# BMS.net
KiCad netlist of a schematic drawn in Altium Designer
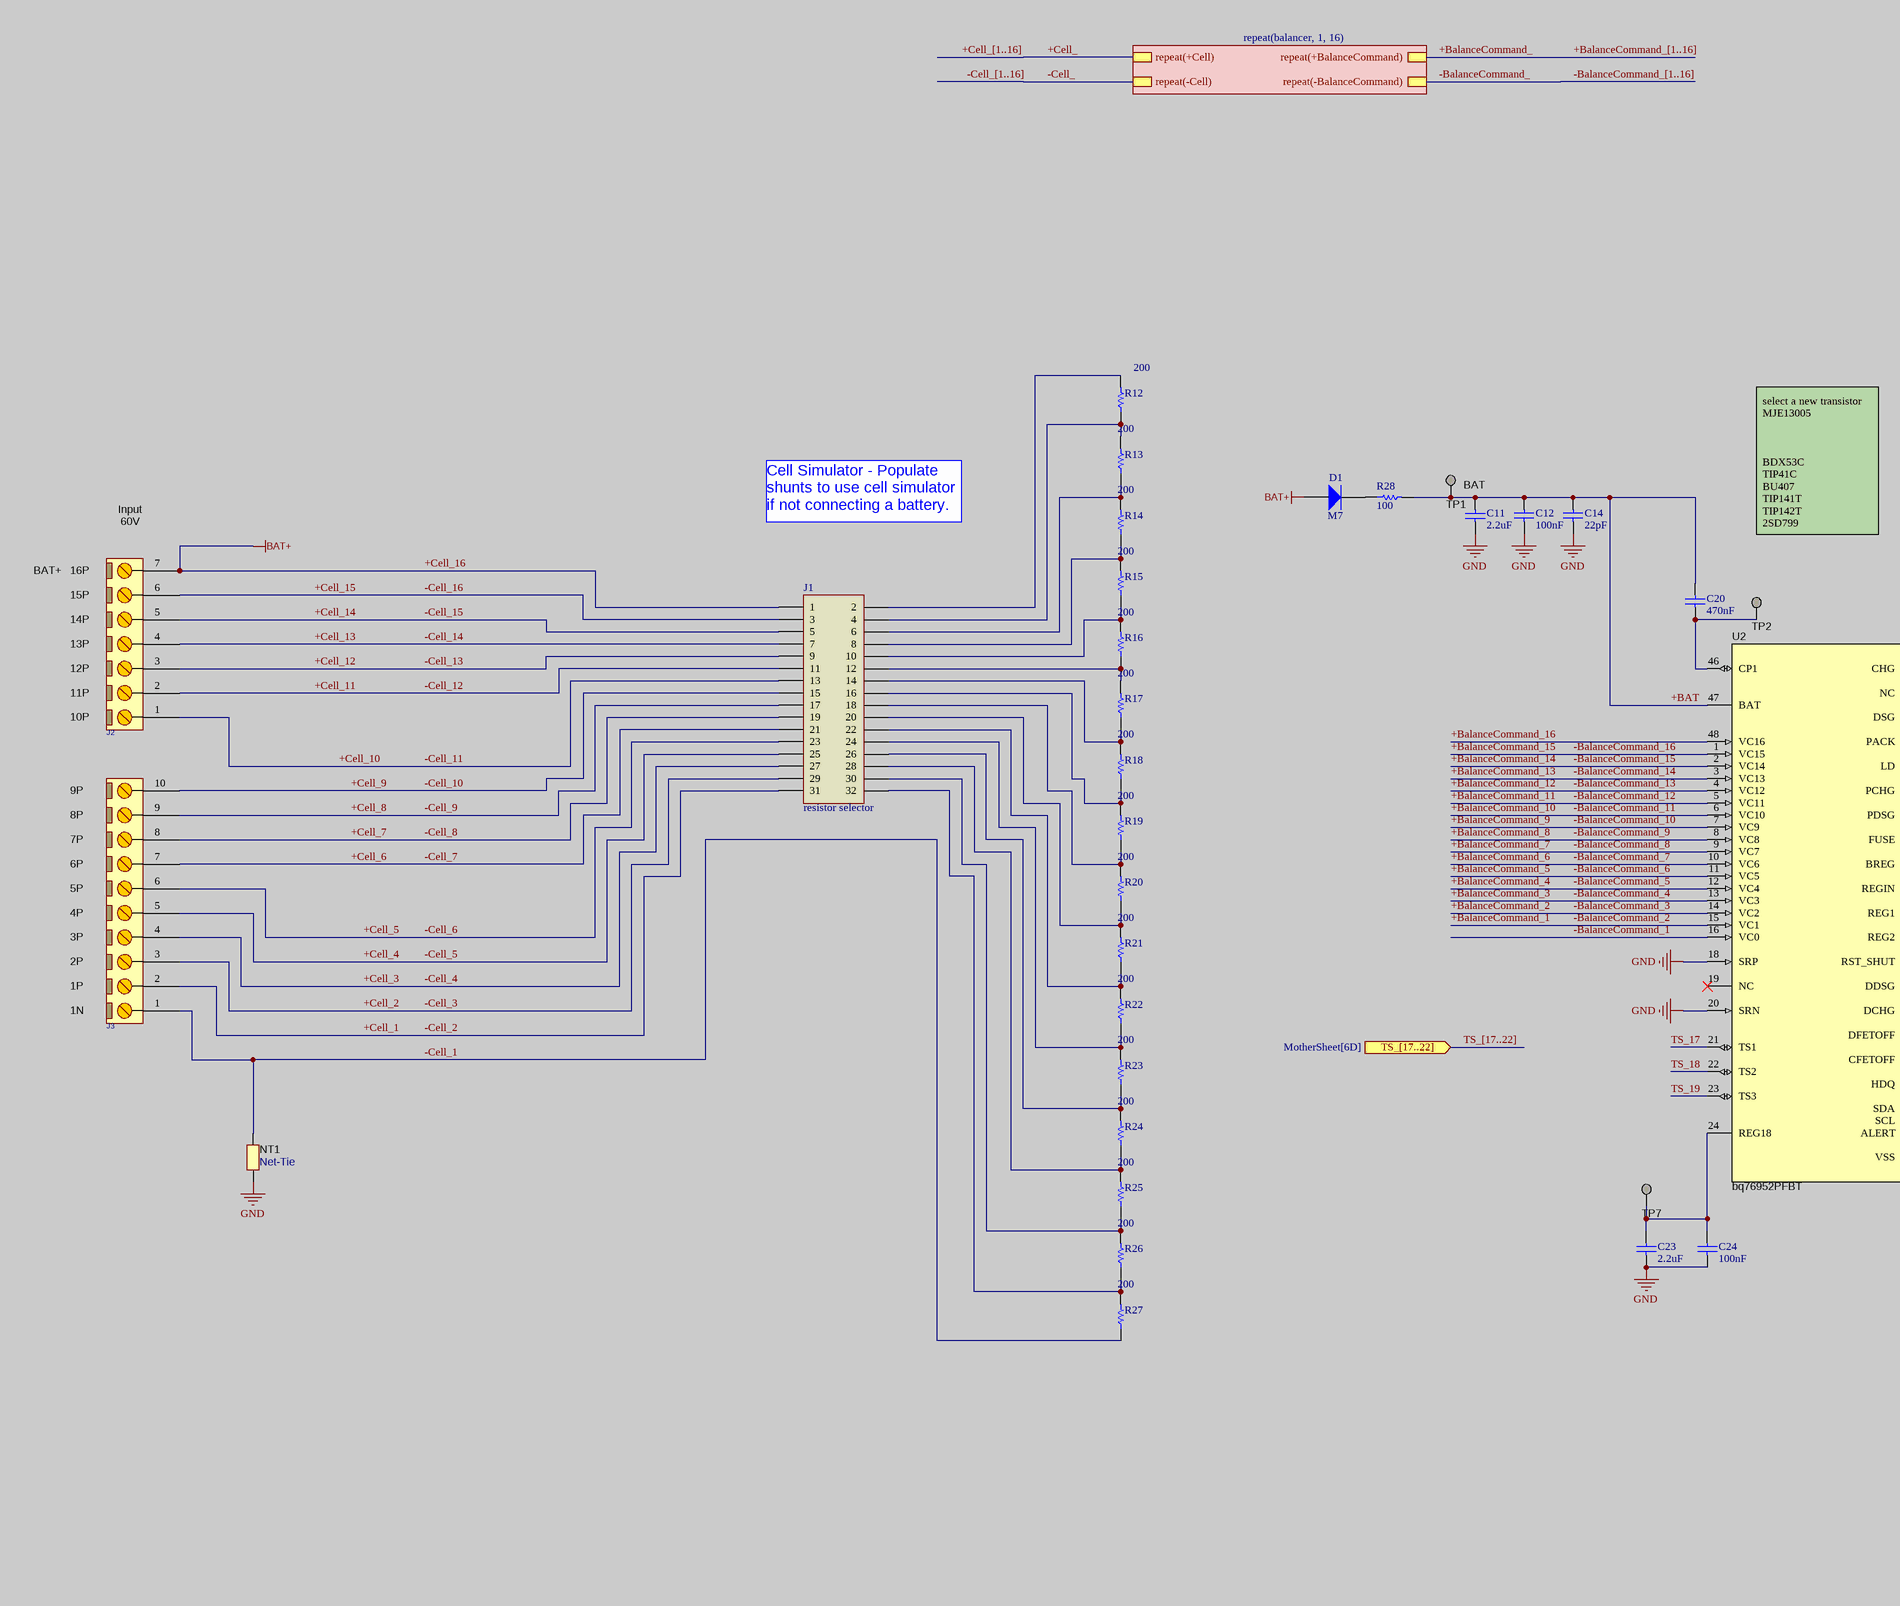
[diagram p0: BMS.SchDoc, left]
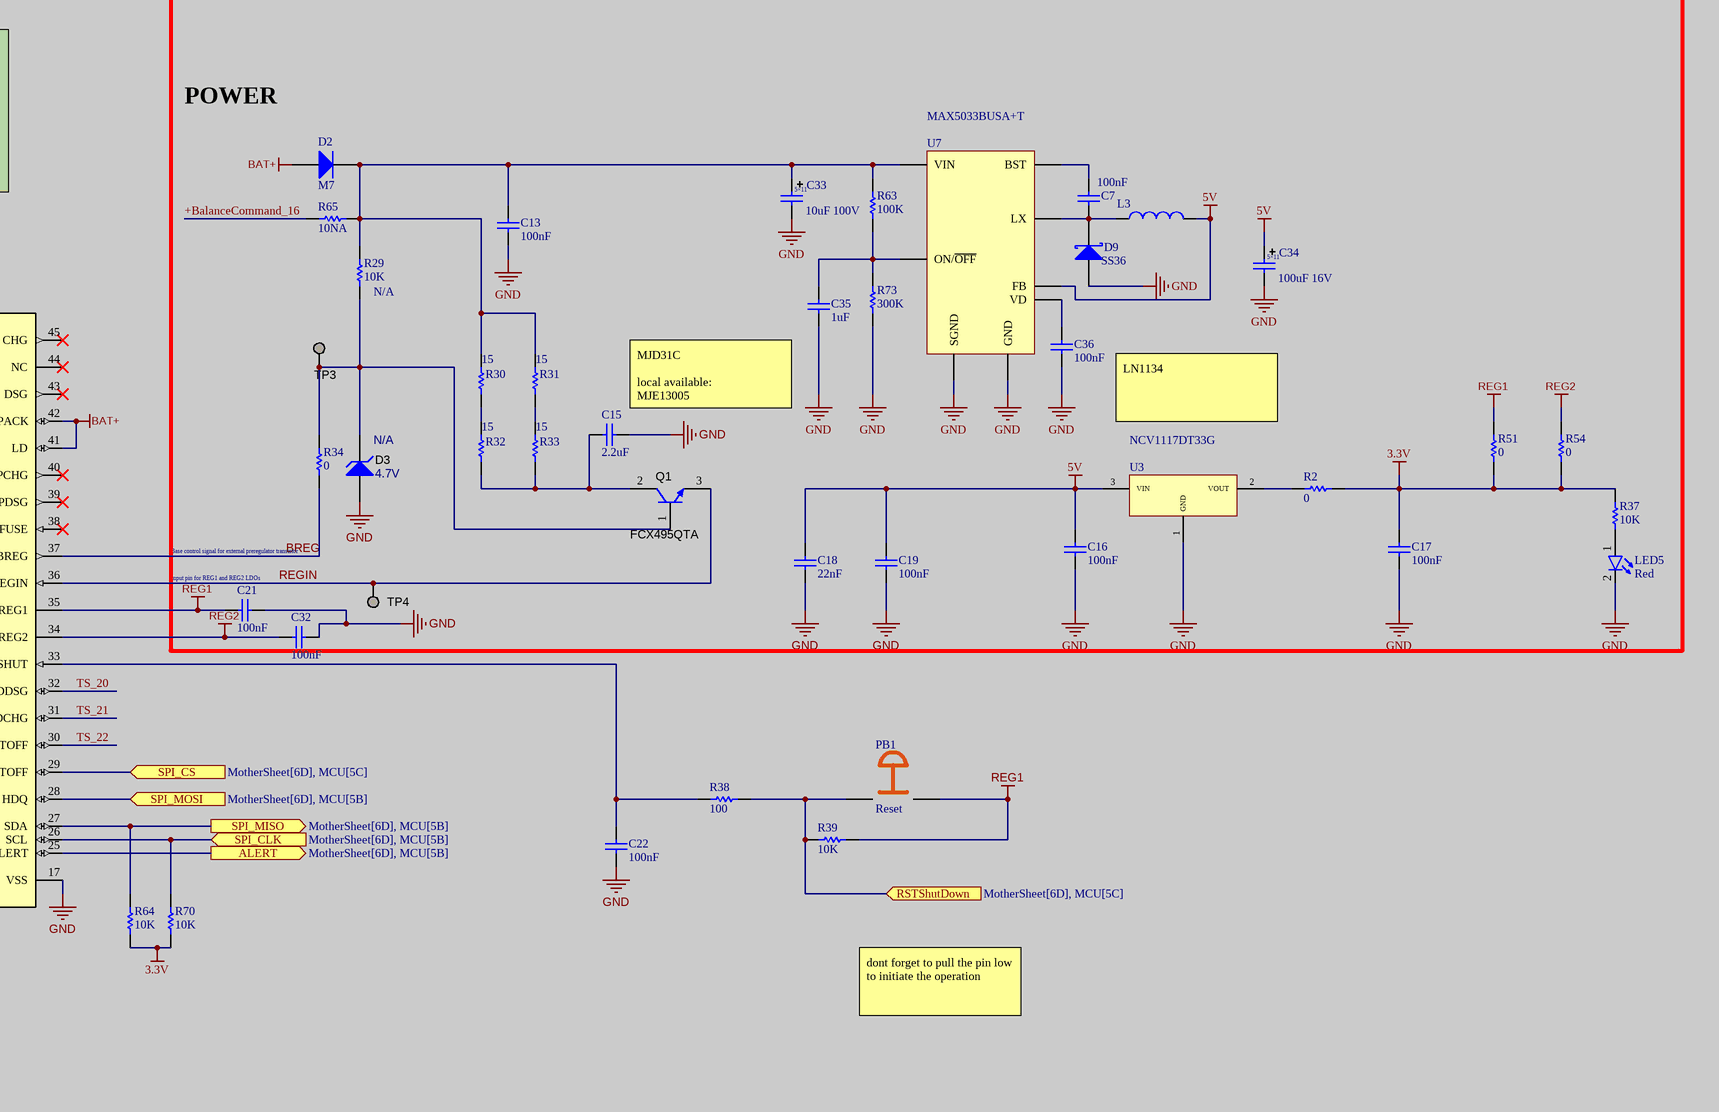
[diagram p1: BMS.SchDoc, right]

(export (version "E")
  (design (tool "Eeschema 10.0.6"))
  (components
    (comp (ref "C7")
      (value "100nF")
      (footprint "CAPC0603")
      (description "100nF-0603")
      (fields (field (name "PUBLISHER") "Altium Limited"))
      (libsource (lib "SINA") (part "Capacitor"))
    )
    (comp (ref "C11")
      (value "2.2uF")
      (footprint "cap1206")
      (description "Capacitor")
      (fields (field (name "PUBLISHER") "Altium Limited"))
      (libsource (lib "eLIB") (part "Capacitor"))
    )
    (comp (ref "C12")
      (value "100nF")
      (footprint "CAPC0603")
      (description "Capacitor")
      (fields (field (name "PUBLISHER") "Altium Limited"))
      (libsource (lib "eLIB") (part "Capacitor"))
    )
    (comp (ref "C13")
      (value "100nF")
      (footprint "CAPC0603")
      (description "Capacitor")
      (fields (field (name "PUBLISHER") "Altium Limited"))
      (libsource (lib "eLIB") (part "Capacitor"))
    )
    (comp (ref "C14")
      (value "22pF")
      (footprint "CAPC0603")
      (description "Capacitor")
      (fields (field (name "PUBLISHER") "Altium Limited"))
      (libsource (lib "eLIB") (part "Capacitor"))
    )
    (comp (ref "C15")
      (value "2.2uF")
      (footprint "cap1206")
      (description "Capacitor")
      (fields (field (name "PUBLISHER") "Altium Limited"))
      (libsource (lib "eLIB") (part "Capacitor"))
    )
    (comp (ref "C16")
      (value "100nF")
      (footprint "CAPC0603")
      (description "Capacitor")
      (fields (field (name "PUBLISHER") "Altium Limited"))
      (libsource (lib "eLIB") (part "Capacitor"))
    )
    (comp (ref "C17")
      (value "100nF")
      (footprint "CAPC0603")
      (description "Capacitor")
      (fields (field (name "PUBLISHER") "Altium Limited"))
      (libsource (lib "eLIB") (part "Capacitor"))
    )
    (comp (ref "C18")
      (value "22nF")
      (footprint "CAPC0603")
      (description "Capacitor")
      (fields (field (name "PUBLISHER") "Altium Limited"))
      (libsource (lib "eLIB") (part "Capacitor"))
    )
    (comp (ref "C19")
      (value "100nF")
      (footprint "CAPC0603")
      (description "Capacitor")
      (fields (field (name "PUBLISHER") "Altium Limited"))
      (libsource (lib "eLIB") (part "Capacitor"))
    )
    (comp (ref "C20")
      (value "470nF")
      (footprint "cap1206")
      (description "Capacitor")
      (fields (field (name "PUBLISHER") "Altium Limited"))
      (libsource (lib "eLIB") (part "Capacitor"))
    )
    (comp (ref "C21")
      (value "100nF")
      (footprint "CAPC0603")
      (description "Capacitor")
      (fields (field (name "PUBLISHER") "Altium Limited"))
      (libsource (lib "eLIB") (part "Capacitor"))
    )
    (comp (ref "C22")
      (value "100nF")
      (footprint "CAPC0603")
      (description "Capacitor")
      (fields (field (name "PUBLISHER") "Altium Limited"))
      (libsource (lib "eLIB") (part "Capacitor"))
    )
    (comp (ref "C23")
      (value "2.2uF")
      (footprint "cap1206")
      (description "Capacitor")
      (fields (field (name "PUBLISHER") "Altium Limited"))
      (libsource (lib "eLIB") (part "Capacitor"))
    )
    (comp (ref "C24")
      (value "100nF")
      (footprint "CAPC0603")
      (description "Capacitor")
      (fields (field (name "PUBLISHER") "Altium Limited"))
      (libsource (lib "eLIB") (part "Capacitor"))
    )
    (comp (ref "C32")
      (value "100nF")
      (footprint "CAPC0603")
      (description "Capacitor")
      (fields (field (name "PUBLISHER") "Altium Limited"))
      (libsource (lib "eLIB") (part "Capacitor"))
    )
    (comp (ref "C33") (value "10uF 100V") (footprint "CAP 5*11") (libsource (lib "SINA") (part "CAP 5*11")))
    (comp (ref "C34") (value "100uF 16V") (footprint "CAP 5*11") (libsource (lib "SINA") (part "CAP 5*11")))
    (comp (ref "C35")
      (value "1uF")
      (footprint "CAPC0603")
      (description "1uF-0603")
      (fields (field (name "PUBLISHER") "Altium Limited"))
      (libsource (lib "SINA") (part "Capacitor"))
    )
    (comp (ref "C36")
      (value "100nF")
      (footprint "CAPC0603")
      (description "100nF-0603")
      (fields (field (name "PUBLISHER") "Altium Limited"))
      (libsource (lib "SINA") (part "Capacitor"))
    )
    (comp (ref "D1") (value "M7") (footprint "SS36") (libsource (lib "SINA") (part "SS36")))
    (comp (ref "D2") (value "M7") (footprint "SS36") (libsource (lib "SINA") (part "SS36")))
    (comp (ref "D3")
      (value "N/A")
      (footprint "ZENER")
      (description "Diode, Zener, 4.7 V, 500 mW")
      (fields
        (field (name "ALTIUM_VALUE") "4.7V")
        (field (name "MANUFACTURER") "ON Semiconductor")
        (field (name "PARTNUMBER") "MMSZ4697T1G")
      )
      (libsource (lib "BMS029B") (part "CMP-0005740-3"))
    )
    (comp (ref "D9")
      (value "SS36")
      (footprint "SS36")
      (description "SS36 -Jled")
      (fields (field (name "PUBLISHER") "Altium Limited"))
      (libsource (lib "SINA") (part "SS34"))
    )
    (comp (ref "J1")
      (value "resistor selector")
      (footprint "SULLINS_PEC10DAAN")
      (description "Header 2*16 LED 2mm")
      (libsource (lib "eLIB") (part "Header 2*16 LED"))
    )
    (comp (ref "J2")
      (value "CONN_TB8")
      (footprint "pheonix_7")
      (description "CONN, TERMINAL BLOCK, 5.08mm pitch")
      (libsource (lib "eLIB") (part "CONN_TB7"))
    )
    (comp (ref "J3")
      (value "CONN_TB8")
      (footprint "pheonix_10")
      (description "CONN, TERMINAL BLOCK, 5.08mm pitch")
      (libsource (lib "eLIB") (part "CONN_TB10"))
    )
    (comp (ref "L3") (value "22uH") (footprint "INDUCTOR 7*7") (libsource (lib "SINA") (part "INDUCTOR 7*7")))
    (comp (ref "LED5")
      (value "Red")
      (footprint "led")
      (description "LED")
      (fields (field (name "COLOR") "Red") (field (name "DESIGNER") "Saeid Jorablo"))
      (libsource (lib "TaraSchlib") (part "LED"))
    )
    (comp (ref "NT1")
      (value "Net-Tie")
      (footprint "Net-Tie_10milWide_30milLong")
      (description "Single point connection between nets.")
      (libsource (lib "eLIB") (part "Net-Tie"))
    )
    (comp (ref "PB1")
      (value "Reset")
      (footprint "SWITCH-PB4")
      (description "4-Pin Push Button")
      (libsource (lib "eLIB") (part "Swtich-PB4"))
    )
    (comp (ref "Q1")
      (value "FCX495QTA")
      (footprint "sot-89")
      (description "BJT 30V 3A 40V 10W SI-NPN")
      (fields
        (field (name "PARTNUMBER") "BSR14")
        (field (name "MANUFACTURER") "Nexperia")
        (field (name "PUBLISHER") "Texas Instruments")
      )
      (libsource (lib "SINA") (part "BSR14, Nexperia"))
    )
    (comp (ref "R2")
      (value "0")
      (footprint "RES0603")
      (description "Resistor")
      (fields (field (name "PUBLISHER") "Altium Limited"))
      (libsource (lib "TaraSchlib") (part "Res"))
    )
    (comp (ref "R12")
      (value "200")
      (footprint "RESC0603")
      (description "0603,0.1W")
      (fields (field (name "PUBLISHER") "Altium Limited"))
      (libsource (lib "eLIB") (part "Resistor"))
    )
    (comp (ref "R13")
      (value "200")
      (footprint "RESC0603")
      (description "0603,0.1W")
      (fields (field (name "PUBLISHER") "Altium Limited"))
      (libsource (lib "eLIB") (part "Resistor"))
    )
    (comp (ref "R14")
      (value "200")
      (footprint "RESC0603")
      (description "0603,0.1W")
      (fields (field (name "PUBLISHER") "Altium Limited"))
      (libsource (lib "eLIB") (part "Resistor"))
    )
    (comp (ref "R15")
      (value "200")
      (footprint "RESC0603")
      (description "0603,0.1W")
      (fields (field (name "PUBLISHER") "Altium Limited"))
      (libsource (lib "eLIB") (part "Resistor"))
    )
    (comp (ref "R16")
      (value "200")
      (footprint "RESC0603")
      (description "0603,0.1W")
      (fields (field (name "PUBLISHER") "Altium Limited"))
      (libsource (lib "eLIB") (part "Resistor"))
    )
    (comp (ref "R17")
      (value "200")
      (footprint "RESC0603")
      (description "0603,0.1W")
      (fields (field (name "PUBLISHER") "Altium Limited"))
      (libsource (lib "eLIB") (part "Resistor"))
    )
    (comp (ref "R18")
      (value "200")
      (footprint "RESC0603")
      (description "0603,0.1W")
      (fields (field (name "PUBLISHER") "Altium Limited"))
      (libsource (lib "eLIB") (part "Resistor"))
    )
    (comp (ref "R19")
      (value "200")
      (footprint "RESC0603")
      (description "0603,0.1W")
      (fields (field (name "PUBLISHER") "Altium Limited"))
      (libsource (lib "eLIB") (part "Resistor"))
    )
    (comp (ref "R20")
      (value "200")
      (footprint "RESC0603")
      (description "0603,0.1W")
      (fields (field (name "PUBLISHER") "Altium Limited"))
      (libsource (lib "eLIB") (part "Resistor"))
    )
    (comp (ref "R21")
      (value "200")
      (footprint "RESC0603")
      (description "0603,0.1W")
      (fields (field (name "PUBLISHER") "Altium Limited"))
      (libsource (lib "eLIB") (part "Resistor"))
    )
    (comp (ref "R22")
      (value "200")
      (footprint "RESC0603")
      (description "0603,0.1W")
      (fields (field (name "PUBLISHER") "Altium Limited"))
      (libsource (lib "eLIB") (part "Resistor"))
    )
    (comp (ref "R23")
      (value "200")
      (footprint "RESC0603")
      (description "0603,0.1W")
      (fields (field (name "PUBLISHER") "Altium Limited"))
      (libsource (lib "eLIB") (part "Resistor"))
    )
    (comp (ref "R24")
      (value "200")
      (footprint "RESC0603")
      (description "0603,0.1W")
      (fields (field (name "PUBLISHER") "Altium Limited"))
      (libsource (lib "eLIB") (part "Resistor"))
    )
    (comp (ref "R25")
      (value "200")
      (footprint "RESC0603")
      (description "0603,0.1W")
      (fields (field (name "PUBLISHER") "Altium Limited"))
      (libsource (lib "eLIB") (part "Resistor"))
    )
    (comp (ref "R26")
      (value "200")
      (footprint "RESC0603")
      (description "0603,0.1W")
      (fields (field (name "PUBLISHER") "Altium Limited"))
      (libsource (lib "eLIB") (part "Resistor"))
    )
    (comp (ref "R27")
      (value "200")
      (footprint "RESC0603")
      (description "0603,0.1W")
      (fields (field (name "PUBLISHER") "Altium Limited"))
      (libsource (lib "eLIB") (part "Resistor"))
    )
    (comp (ref "R28")
      (value "100")
      (footprint "RESC0603")
      (description "0603,0.1W")
      (fields (field (name "PUBLISHER") "Altium Limited"))
      (libsource (lib "eLIB") (part "Resistor"))
    )
    (comp (ref "R29")
      (value "N/A")
      (footprint "RES0603")
      (description "Resistor")
      (fields (field (name "ALTIUM_VALUE") "10K") (field (name "PUBLISHER") "Altium Limited"))
      (libsource (lib "TaraSchlib") (part "Res"))
    )
    (comp (ref "R30")
      (value "15")
      (footprint "RES2512")
      (description "0603,0.1W")
      (fields (field (name "PUBLISHER") "Altium Limited"))
      (libsource (lib "BMS029B") (part "Resistor_2"))
    )
    (comp (ref "R31")
      (value "15")
      (footprint "RES2512")
      (description "0603,0.1W")
      (fields (field (name "PUBLISHER") "Altium Limited"))
      (libsource (lib "BMS029B") (part "Resistor_2"))
    )
    (comp (ref "R32")
      (value "15")
      (footprint "RES2512")
      (description "0603,0.1W")
      (fields (field (name "PUBLISHER") "Altium Limited"))
      (libsource (lib "BMS029B") (part "Resistor_2"))
    )
    (comp (ref "R33")
      (value "15")
      (footprint "RES2512")
      (description "0603,0.1W")
      (fields (field (name "PUBLISHER") "Altium Limited"))
      (libsource (lib "BMS029B") (part "Resistor_2"))
    )
    (comp (ref "R34")
      (value "0")
      (footprint "RES0603")
      (description "Resistor")
      (fields (field (name "PUBLISHER") "Altium Limited"))
      (libsource (lib "TaraSchlib") (part "Res"))
    )
    (comp (ref "R37")
      (value "10K")
      (footprint "RES0603")
      (description "Resistor")
      (fields (field (name "PUBLISHER") "Altium Limited"))
      (libsource (lib "TaraSchlib") (part "Res"))
    )
    (comp (ref "R38")
      (value "100")
      (footprint "RES0603")
      (description "Resistor")
      (fields (field (name "PUBLISHER") "Altium Limited"))
      (libsource (lib "TaraSchlib") (part "Res"))
    )
    (comp (ref "R39")
      (value "10K")
      (footprint "RES0603")
      (description "Resistor")
      (fields (field (name "PUBLISHER") "Altium Limited"))
      (libsource (lib "TaraSchlib") (part "Res"))
    )
    (comp (ref "R51")
      (value "0")
      (footprint "RES0603")
      (description "Resistor")
      (fields (field (name "PUBLISHER") "Altium Limited"))
      (libsource (lib "TaraSchlib") (part "Res"))
    )
    (comp (ref "R54")
      (value "0")
      (footprint "RES0603")
      (description "Resistor")
      (fields (field (name "PUBLISHER") "Altium Limited"))
      (libsource (lib "TaraSchlib") (part "Res"))
    )
    (comp (ref "R63")
      (value "100K")
      (footprint "RESC0603")
      (description "100K-0603")
      (fields (field (name "PUBLISHER") "Altium Limited"))
      (libsource (lib "SINA") (part "Resistor"))
    )
    (comp (ref "R64")
      (value "10K")
      (footprint "RES0603")
      (description "Resistor")
      (fields (field (name "PUBLISHER") "Altium Limited"))
      (libsource (lib "TaraSchlib") (part "Res"))
    )
    (comp (ref "R65")
      (value "10NA")
      (footprint "RES0603")
      (description "Resistor")
      (fields (field (name "PUBLISHER") "Altium Limited"))
      (libsource (lib "TaraSchlib") (part "Res"))
    )
    (comp (ref "R70")
      (value "10K")
      (footprint "RES0603")
      (description "Resistor")
      (fields (field (name "PUBLISHER") "Altium Limited"))
      (libsource (lib "TaraSchlib") (part "Res"))
    )
    (comp (ref "R73")
      (value "300K")
      (footprint "RESC0603")
      (description "300K-0603")
      (fields (field (name "PUBLISHER") "Altium Limited"))
      (libsource (lib "SINA") (part "Resistor"))
    )
    (comp (ref "TP1")
      (value "TESTPOINT")
      (footprint "Test Point")
      (description "TEST POINT.  No entry in BOM.")
      (libsource (lib "eLIB") (part "TESTPOINT"))
    )
    (comp (ref "TP2")
      (value "TESTPOINT")
      (footprint "Test Point")
      (description "TEST POINT.  No entry in BOM.")
      (libsource (lib "eLIB") (part "TESTPOINT"))
    )
    (comp (ref "TP3")
      (value "TESTPOINT")
      (footprint "Test Point")
      (description "TEST POINT.  No entry in BOM.")
      (libsource (lib "eLIB") (part "TESTPOINT"))
    )
    (comp (ref "TP4")
      (value "TESTPOINT")
      (footprint "Test Point")
      (description "TEST POINT.  No entry in BOM.")
      (libsource (lib "eLIB") (part "TESTPOINT"))
    )
    (comp (ref "TP7")
      (value "TESTPOINT")
      (footprint "Test Point")
      (description "TEST POINT.  No entry in BOM.")
      (libsource (lib "eLIB") (part "TESTPOINT"))
    )
    (comp (ref "U2")
      (value "bq76952PFBT")
      (footprint "STM32F103C8T6")
      (description "Multicell Battery Monitor and Protection Family, PFB0048A (TQFP-48)")
      (fields
        (field (name "ALTERNATE PARTNUMBER") "bq76952PFBR")
        (field (name "MANUFACTURER") "Texas Instruments")
        (field (name "PARTNUMBER") "bq76952PFBT")
      )
      (libsource (lib "eLIB") (part "bq76952"))
    )
    (comp (ref "U3")
      (value "NCV1117DT33G")
      (footprint "AMS1117")
      (description "High Accuracy, Ultralow IQ, 1.5 A, anyCAP Low Dropout Regulator")
      (libsource (lib "eLIB") (part "AMS1117"))
    )
    (comp (ref "U7")
      (value "MAX5033BUSA+T")
      (footprint "SINA:SOIC8")
      (description "High-Efficiency, MAXPower    Step-Down DC-DC Converter")
      (libsource (lib "SINA") (part "MAX5033"))
    )
  )
  (nets
    (net (code "1") (name "/+BAT") (class "Default")
      (node (ref "C11") (pin "1") (pinfunction "1_1") (pintype "passive"))
      (node (ref "C12") (pin "2") (pinfunction "2_2") (pintype "passive"))
      (node (ref "C14") (pin "2") (pinfunction "2_2") (pintype "passive"))
      (node (ref "C20") (pin "1") (pinfunction "1_1") (pintype "passive"))
      (node (ref "R28") (pin "2") (pinfunction "2_2") (pintype "passive"))
      (node (ref "TP1") (pin "1") (pintype "passive"))
      (node (ref "U2") (pin "47") (pinfunction "BAT_47") (pintype "power_in"))
    )
    (net (code "3") (name "/+BalanceCommand_16") (class "Default")
      (node (ref "R65") (pin "1") (pinfunction "1_1") (pintype "passive"))
      (node (ref "U2") (pin "48") (pinfunction "VC16_48") (pintype "input"))
    )
    (net (code "8") (name "/-BalanceCommand_1") (class "Default")
      (node (ref "U2") (pin "16") (pinfunction "VC0_16") (pintype "input"))
    )
    (net (code "9") (name "/-BalanceCommand_2") (class "Default")
      (node (ref "U2") (pin "15") (pinfunction "VC1_15") (pintype "input"))
    )
    (net (code "10") (name "/-BalanceCommand_3") (class "Default")
      (node (ref "U2") (pin "14") (pinfunction "VC2_14") (pintype "input"))
    )
    (net (code "11") (name "/-BalanceCommand_4") (class "Default")
      (node (ref "U2") (pin "13") (pinfunction "VC3_13") (pintype "input"))
    )
    (net (code "12") (name "/-BalanceCommand_5") (class "Default")
      (node (ref "U2") (pin "12") (pinfunction "VC4_12") (pintype "input"))
    )
    (net (code "13") (name "/-BalanceCommand_6") (class "Default")
      (node (ref "U2") (pin "11") (pinfunction "VC5_11") (pintype "input"))
    )
    (net (code "14") (name "/-BalanceCommand_7") (class "Default")
      (node (ref "U2") (pin "10") (pinfunction "VC6_10") (pintype "input"))
    )
    (net (code "15") (name "/-BalanceCommand_8") (class "Default")
      (node (ref "U2") (pin "9") (pinfunction "VC7_9") (pintype "input"))
    )
    (net (code "16") (name "/-BalanceCommand_9") (class "Default")
      (node (ref "U2") (pin "8") (pinfunction "VC8_8") (pintype "input"))
    )
    (net (code "17") (name "/-BalanceCommand_10") (class "Default")
      (node (ref "U2") (pin "7") (pinfunction "VC9_7") (pintype "input"))
    )
    (net (code "18") (name "/-BalanceCommand_11") (class "Default")
      (node (ref "U2") (pin "6") (pinfunction "VC10_6") (pintype "input"))
    )
    (net (code "19") (name "/-BalanceCommand_12") (class "Default")
      (node (ref "U2") (pin "5") (pinfunction "VC11_5") (pintype "input"))
    )
    (net (code "20") (name "/-BalanceCommand_13") (class "Default")
      (node (ref "U2") (pin "4") (pinfunction "VC12_4") (pintype "input"))
    )
    (net (code "21") (name "/-BalanceCommand_14") (class "Default")
      (node (ref "U2") (pin "3") (pinfunction "VC13_3") (pintype "input"))
    )
    (net (code "22") (name "/-BalanceCommand_15") (class "Default")
      (node (ref "U2") (pin "2") (pinfunction "VC14_2") (pintype "input"))
    )
    (net (code "23") (name "/-BalanceCommand_16") (class "Default")
      (node (ref "U2") (pin "1") (pinfunction "VC15_1") (pintype "input"))
    )
    (net (code "26") (name "/-Cell_1") (class "Default")
      (node (ref "J3") (pin "1") (pinfunction "1_1") (pintype "passive"))
      (node (ref "NT1") (pin "1") (pinfunction "1_1") (pintype "passive"))
      (node (ref "R27") (pin "1") (pinfunction "1_1") (pintype "passive"))
    )
    (net (code "27") (name "/-Cell_2") (class "Default")
      (node (ref "J1") (pin "31") (pinfunction "31_31") (pintype "passive"))
      (node (ref "J3") (pin "2") (pinfunction "2_2") (pintype "passive"))
    )
    (net (code "28") (name "/-Cell_3") (class "Default")
      (node (ref "J1") (pin "29") (pinfunction "29_29") (pintype "passive"))
      (node (ref "J3") (pin "3") (pinfunction "3_3") (pintype "passive"))
    )
    (net (code "29") (name "/-Cell_4") (class "Default")
      (node (ref "J1") (pin "27") (pinfunction "27_27") (pintype "passive"))
      (node (ref "J3") (pin "4") (pinfunction "4_4") (pintype "passive"))
    )
    (net (code "30") (name "/-Cell_5") (class "Default")
      (node (ref "J1") (pin "25") (pinfunction "25_25") (pintype "passive"))
      (node (ref "J3") (pin "5") (pinfunction "5_5") (pintype "passive"))
    )
    (net (code "31") (name "/-Cell_6") (class "Default")
      (node (ref "J1") (pin "23") (pinfunction "23_23") (pintype "passive"))
      (node (ref "J3") (pin "6") (pinfunction "6_6") (pintype "passive"))
    )
    (net (code "32") (name "/-Cell_7") (class "Default")
      (node (ref "J1") (pin "21") (pinfunction "21_21") (pintype "passive"))
      (node (ref "J3") (pin "7") (pinfunction "7_7") (pintype "passive"))
    )
    (net (code "33") (name "/-Cell_8") (class "Default")
      (node (ref "J1") (pin "19") (pinfunction "19_19") (pintype "passive"))
      (node (ref "J3") (pin "8") (pinfunction "8_8") (pintype "passive"))
    )
    (net (code "34") (name "/-Cell_9") (class "Default")
      (node (ref "J1") (pin "17") (pinfunction "17_17") (pintype "passive"))
      (node (ref "J3") (pin "9") (pinfunction "9_9") (pintype "passive"))
    )
    (net (code "35") (name "/-Cell_10") (class "Default")
      (node (ref "J1") (pin "15") (pinfunction "15_15") (pintype "passive"))
      (node (ref "J3") (pin "10") (pinfunction "10_10") (pintype "passive"))
    )
    (net (code "36") (name "/-Cell_11") (class "Default")
      (node (ref "J1") (pin "13") (pinfunction "13_13") (pintype "passive"))
      (node (ref "J2") (pin "1") (pinfunction "1_1") (pintype "passive"))
    )
    (net (code "37") (name "/-Cell_12") (class "Default")
      (node (ref "J1") (pin "11") (pinfunction "11_11") (pintype "passive"))
      (node (ref "J2") (pin "2") (pinfunction "2_2") (pintype "passive"))
    )
    (net (code "38") (name "/-Cell_13") (class "Default")
      (node (ref "J1") (pin "9") (pinfunction "9_9") (pintype "passive"))
      (node (ref "J2") (pin "3") (pinfunction "3_3") (pintype "passive"))
    )
    (net (code "39") (name "/-Cell_14") (class "Default")
      (node (ref "J1") (pin "7") (pinfunction "7_7") (pintype "passive"))
      (node (ref "J2") (pin "4") (pinfunction "4_4") (pintype "passive"))
    )
    (net (code "40") (name "/-Cell_15") (class "Default")
      (node (ref "J1") (pin "5") (pinfunction "5_5") (pintype "passive"))
      (node (ref "J2") (pin "5") (pinfunction "5_5") (pintype "passive"))
    )
    (net (code "41") (name "/-Cell_16") (class "Default")
      (node (ref "J1") (pin "3") (pinfunction "3_3") (pintype "passive"))
      (node (ref "J2") (pin "6") (pinfunction "6_6") (pintype "passive"))
    )
    (net (code "44") (name "/ALERT") (class "Default")
      (node (ref "U2") (pin "25") (pinfunction "ALERT_25") (pintype "bidirectional"))
    )
    (net (code "45") (name "/BREG") (class "Default")
      (node (ref "R34") (pin "2") (pinfunction "2_2") (pintype "passive"))
      (node (ref "U2") (pin "37") (pinfunction "BREG_37") (pintype "output"))
    )
    (net (code "46") (name "/REGIN") (class "Default")
      (node (ref "Q1") (pin "3") (pinfunction "E_3") (pintype "passive"))
      (node (ref "TP4") (pin "1") (pintype "passive"))
      (node (ref "U2") (pin "36") (pinfunction "REGIN_36") (pintype "input"))
    )
    (net (code "47") (name "/RSTShutDown") (class "Default")
      (node (ref "PB1") (pin "1") (pinfunction "1_1") (pintype "passive"))
      (node (ref "R38") (pin "2") (pinfunction "2_2") (pintype "passive"))
      (node (ref "R39") (pin "1") (pinfunction "1_1") (pintype "passive"))
    )
    (net (code "48") (name "/SPI_CLK") (class "Default")
      (node (ref "R70") (pin "1") (pinfunction "1_1") (pintype "passive"))
      (node (ref "U2") (pin "26") (pinfunction "SCL_26") (pintype "bidirectional"))
    )
    (net (code "49") (name "/SPI_CS") (class "Default")
      (node (ref "U2") (pin "29") (pinfunction "CFETOFF_29") (pintype "bidirectional"))
    )
    (net (code "50") (name "/SPI_MISO") (class "Default")
      (node (ref "R64") (pin "1") (pinfunction "1_1") (pintype "passive"))
      (node (ref "U2") (pin "27") (pinfunction "SDA_27") (pintype "bidirectional"))
    )
    (net (code "51") (name "/SPI_MOSI") (class "Default")
      (node (ref "U2") (pin "28") (pinfunction "HDQ_28") (pintype "bidirectional"))
    )
    (net (code "52") (name "/TS_17") (class "Default")
      (node (ref "U2") (pin "21") (pinfunction "TS1_21") (pintype "bidirectional"))
    )
    (net (code "53") (name "/TS_18") (class "Default")
      (node (ref "U2") (pin "22") (pinfunction "TS2_22") (pintype "bidirectional"))
    )
    (net (code "54") (name "/TS_19") (class "Default")
      (node (ref "U2") (pin "23") (pinfunction "TS3_23") (pintype "bidirectional"))
    )
    (net (code "55") (name "/TS_20") (class "Default")
      (node (ref "U2") (pin "32") (pinfunction "DDSG_32") (pintype "bidirectional"))
    )
    (net (code "56") (name "/TS_21") (class "Default")
      (node (ref "U2") (pin "31") (pinfunction "DCHG_31") (pintype "bidirectional"))
    )
    (net (code "57") (name "/TS_22") (class "Default")
      (node (ref "U2") (pin "30") (pinfunction "DFETOFF_30") (pintype "bidirectional"))
    )
    (net (code "59") (name "3.3V") (class "Default")
      (node (ref "C17") (pin "2") (pinfunction "2_2") (pintype "passive"))
      (node (ref "R2") (pin "2") (pinfunction "2_2") (pintype "passive"))
      (node (ref "R37") (pin "1") (pinfunction "1_1") (pintype "passive"))
      (node (ref "R51") (pin "1") (pinfunction "1_1") (pintype "passive"))
      (node (ref "R54") (pin "1") (pinfunction "1_1") (pintype "passive"))
      (node (ref "R64") (pin "2") (pinfunction "2_2") (pintype "passive"))
      (node (ref "R70") (pin "2") (pinfunction "2_2") (pintype "passive"))
    )
    (net (code "60") (name "5V") (class "Default")
      (node (ref "C16") (pin "2") (pinfunction "2_2") (pintype "passive"))
      (node (ref "C18") (pin "2") (pinfunction "2_2") (pintype "passive"))
      (node (ref "C19") (pin "2") (pinfunction "2_2") (pintype "passive"))
      (node (ref "C34") (pin "2") (pinfunction "1_2") (pintype "passive"))
      (node (ref "L3") (pin "2") (pinfunction "2_2") (pintype "passive"))
      (node (ref "U3") (pin "3") (pinfunction "VIN_3") (pintype "passive"))
      (node (ref "U7") (pin "4") (pinfunction "FB_4") (pintype "passive"))
    )
    (net (code "61") (name "BAT+") (class "Default")
      (node (ref "D1") (pin "1") (pinfunction "A_1") (pintype "passive"))
      (node (ref "D2") (pin "1") (pinfunction "A_1") (pintype "passive"))
      (node (ref "J1") (pin "1") (pinfunction "1_1") (pintype "passive"))
      (node (ref "J2") (pin "7") (pinfunction "7_7") (pintype "passive"))
      (node (ref "U2") (pin "41") (pinfunction "LD_41") (pintype "bidirectional"))
      (node (ref "U2") (pin "42") (pinfunction "PACK_42") (pintype "bidirectional"))
    )
    (net (code "62") (name "GND") (class "Default")
      (node (ref "C11") (pin "2") (pinfunction "2_2") (pintype "passive"))
      (node (ref "C12") (pin "1") (pinfunction "1_1") (pintype "passive"))
      (node (ref "C13") (pin "1") (pinfunction "1_1") (pintype "passive"))
      (node (ref "C14") (pin "1") (pinfunction "1_1") (pintype "passive"))
      (node (ref "C15") (pin "1") (pinfunction "1_1") (pintype "passive"))
      (node (ref "C16") (pin "1") (pinfunction "1_1") (pintype "passive"))
      (node (ref "C17") (pin "1") (pinfunction "1_1") (pintype "passive"))
      (node (ref "C18") (pin "1") (pinfunction "1_1") (pintype "passive"))
      (node (ref "C19") (pin "1") (pinfunction "1_1") (pintype "passive"))
      (node (ref "C21") (pin "2") (pinfunction "2_2") (pintype "passive"))
      (node (ref "C22") (pin "1") (pinfunction "1_1") (pintype "passive"))
      (node (ref "C23") (pin "1") (pinfunction "1_1") (pintype "passive"))
      (node (ref "C24") (pin "1") (pinfunction "1_1") (pintype "passive"))
      (node (ref "C32") (pin "2") (pinfunction "2_2") (pintype "passive"))
      (node (ref "C33") (pin "1") (pinfunction "2_1") (pintype "passive"))
      (node (ref "C34") (pin "1") (pinfunction "2_1") (pintype "passive"))
      (node (ref "C35") (pin "1") (pinfunction "1_1") (pintype "passive"))
      (node (ref "C36") (pin "1") (pinfunction "1_1") (pintype "passive"))
      (node (ref "D3") (pin "2") (pinfunction "A_2") (pintype "passive"))
      (node (ref "D9") (pin "1") (pinfunction "A_1") (pintype "passive"))
      (node (ref "LED5") (pin "2") (pinfunction "K_2") (pintype "passive"))
      (node (ref "NT1") (pin "2") (pinfunction "2_2") (pintype "passive"))
      (node (ref "R73") (pin "1") (pinfunction "1_1") (pintype "passive"))
      (node (ref "U2") (pin "17") (pinfunction "VSS_17") (pintype "power_in"))
      (node (ref "U2") (pin "18") (pinfunction "SRP_18") (pintype "input"))
      (node (ref "U2") (pin "20") (pinfunction "SRN_20") (pintype "input"))
      (node (ref "U3") (pin "1") (pinfunction "GND_1") (pintype "passive"))
      (node (ref "U7") (pin "3") (pinfunction "SGND_3") (pintype "passive"))
      (node (ref "U7") (pin "6") (pinfunction "GND_6") (pintype "passive"))
    )
    (net (code "63") (name "Net-(C33-1)") (class "Default")
      (node (ref "C13") (pin "2") (pinfunction "2_2") (pintype "passive"))
      (node (ref "C33") (pin "2") (pinfunction "1_2") (pintype "passive"))
      (node (ref "D2") (pin "2") (pinfunction "K_2") (pintype "passive"))
      (node (ref "R29") (pin "1") (pinfunction "1_1") (pintype "passive"))
      (node (ref "R30") (pin "2") (pinfunction "2_2") (pintype "passive"))
      (node (ref "R31") (pin "2") (pinfunction "2_2") (pintype "passive"))
      (node (ref "R63") (pin "2") (pinfunction "2_2") (pintype "passive"))
      (node (ref "R65") (pin "2") (pinfunction "2_2") (pintype "passive"))
      (node (ref "U7") (pin "7") (pinfunction "VIN_7") (pintype "passive"))
    )
    (net (code "64") (name "Net-(D1-K)") (class "Default")
      (node (ref "D1") (pin "2") (pinfunction "K_2") (pintype "passive"))
      (node (ref "R28") (pin "1") (pinfunction "1_1") (pintype "passive"))
    )
    (net (code "65") (name "Net-(D3-K)") (class "Default")
      (node (ref "D3") (pin "1") (pinfunction "K_1") (pintype "passive"))
      (node (ref "Q1") (pin "1") (pinfunction "B_1") (pintype "passive"))
      (node (ref "R29") (pin "2") (pinfunction "2_2") (pintype "passive"))
      (node (ref "R34") (pin "1") (pinfunction "1_1") (pintype "passive"))
      (node (ref "TP3") (pin "1") (pintype "passive"))
    )
    (net (code "66") (name "Net-(D9-K)") (class "Default")
      (node (ref "C7") (pin "1") (pinfunction "1_1") (pintype "passive"))
      (node (ref "D9") (pin "2") (pinfunction "K_2") (pintype "passive"))
      (node (ref "L3") (pin "1") (pinfunction "1_1") (pintype "passive"))
      (node (ref "U7") (pin "8") (pinfunction "LX_8") (pintype "passive"))
    )
    (net (code "67") (name "Net-(J1-Pad2)") (class "Default")
      (node (ref "J1") (pin "2") (pinfunction "2_2") (pintype "passive"))
      (node (ref "R12") (pin "2") (pinfunction "2_2") (pintype "passive"))
    )
    (net (code "68") (name "Net-(J1-Pad4)") (class "Default")
      (node (ref "J1") (pin "4") (pinfunction "4_4") (pintype "passive"))
      (node (ref "R12") (pin "1") (pinfunction "1_1") (pintype "passive"))
      (node (ref "R13") (pin "2") (pinfunction "2_2") (pintype "passive"))
    )
    (net (code "69") (name "Net-(J1-Pad6)") (class "Default")
      (node (ref "J1") (pin "6") (pinfunction "6_6") (pintype "passive"))
      (node (ref "R13") (pin "1") (pinfunction "1_1") (pintype "passive"))
      (node (ref "R14") (pin "2") (pinfunction "2_2") (pintype "passive"))
    )
    (net (code "70") (name "Net-(J1-Pad8)") (class "Default")
      (node (ref "J1") (pin "8") (pinfunction "8_8") (pintype "passive"))
      (node (ref "R14") (pin "1") (pinfunction "1_1") (pintype "passive"))
      (node (ref "R15") (pin "2") (pinfunction "2_2") (pintype "passive"))
    )
    (net (code "71") (name "Net-(J1-Pad10)") (class "Default")
      (node (ref "J1") (pin "10") (pinfunction "10_10") (pintype "passive"))
      (node (ref "R15") (pin "1") (pinfunction "1_1") (pintype "passive"))
      (node (ref "R16") (pin "2") (pinfunction "2_2") (pintype "passive"))
    )
    (net (code "72") (name "Net-(J1-Pad12)") (class "Default")
      (node (ref "J1") (pin "12") (pinfunction "12_12") (pintype "passive"))
      (node (ref "R16") (pin "1") (pinfunction "1_1") (pintype "passive"))
      (node (ref "R17") (pin "2") (pinfunction "2_2") (pintype "passive"))
    )
    (net (code "73") (name "Net-(J1-Pad14)") (class "Default")
      (node (ref "J1") (pin "14") (pinfunction "14_14") (pintype "passive"))
      (node (ref "R17") (pin "1") (pinfunction "1_1") (pintype "passive"))
      (node (ref "R18") (pin "2") (pinfunction "2_2") (pintype "passive"))
    )
    (net (code "74") (name "Net-(J1-Pad16)") (class "Default")
      (node (ref "J1") (pin "16") (pinfunction "16_16") (pintype "passive"))
      (node (ref "R18") (pin "1") (pinfunction "1_1") (pintype "passive"))
      (node (ref "R19") (pin "2") (pinfunction "2_2") (pintype "passive"))
    )
    (net (code "75") (name "Net-(J1-Pad18)") (class "Default")
      (node (ref "J1") (pin "18") (pinfunction "18_18") (pintype "passive"))
      (node (ref "R19") (pin "1") (pinfunction "1_1") (pintype "passive"))
      (node (ref "R20") (pin "2") (pinfunction "2_2") (pintype "passive"))
    )
    (net (code "76") (name "Net-(J1-Pad20)") (class "Default")
      (node (ref "J1") (pin "20") (pinfunction "20_20") (pintype "passive"))
      (node (ref "R20") (pin "1") (pinfunction "1_1") (pintype "passive"))
      (node (ref "R21") (pin "2") (pinfunction "2_2") (pintype "passive"))
    )
    (net (code "77") (name "Net-(J1-Pad22)") (class "Default")
      (node (ref "J1") (pin "22") (pinfunction "22_22") (pintype "passive"))
      (node (ref "R21") (pin "1") (pinfunction "1_1") (pintype "passive"))
      (node (ref "R22") (pin "2") (pinfunction "2_2") (pintype "passive"))
    )
    (net (code "78") (name "Net-(J1-Pad24)") (class "Default")
      (node (ref "J1") (pin "24") (pinfunction "24_24") (pintype "passive"))
      (node (ref "R22") (pin "1") (pinfunction "1_1") (pintype "passive"))
      (node (ref "R23") (pin "2") (pinfunction "2_2") (pintype "passive"))
    )
    (net (code "79") (name "Net-(J1-Pad26)") (class "Default")
      (node (ref "J1") (pin "26") (pinfunction "26_26") (pintype "passive"))
      (node (ref "R23") (pin "1") (pinfunction "1_1") (pintype "passive"))
      (node (ref "R24") (pin "2") (pinfunction "2_2") (pintype "passive"))
    )
    (net (code "80") (name "Net-(J1-Pad28)") (class "Default")
      (node (ref "J1") (pin "28") (pinfunction "28_28") (pintype "passive"))
      (node (ref "R24") (pin "1") (pinfunction "1_1") (pintype "passive"))
      (node (ref "R25") (pin "2") (pinfunction "2_2") (pintype "passive"))
    )
    (net (code "81") (name "Net-(J1-Pad30)") (class "Default")
      (node (ref "J1") (pin "30") (pinfunction "30_30") (pintype "passive"))
      (node (ref "R25") (pin "1") (pinfunction "1_1") (pintype "passive"))
      (node (ref "R26") (pin "2") (pinfunction "2_2") (pintype "passive"))
    )
    (net (code "82") (name "Net-(J1-Pad32)") (class "Default")
      (node (ref "J1") (pin "32") (pinfunction "32_32") (pintype "passive"))
      (node (ref "R26") (pin "1") (pinfunction "1_1") (pintype "passive"))
      (node (ref "R27") (pin "2") (pinfunction "2_2") (pintype "passive"))
    )
    (net (code "83") (name "Net-(LED5-A)") (class "Default")
      (node (ref "LED5") (pin "1") (pinfunction "A_1") (pintype "passive"))
      (node (ref "R37") (pin "2") (pinfunction "2_2") (pintype "passive"))
    )
    (net (code "84") (name "Net-(Q1-C)") (class "Default")
      (node (ref "C15") (pin "2") (pinfunction "2_2") (pintype "passive"))
      (node (ref "Q1") (pin "2") (pinfunction "C_2") (pintype "passive"))
      (node (ref "R32") (pin "1") (pinfunction "1_1") (pintype "passive"))
      (node (ref "R33") (pin "1") (pinfunction "1_1") (pintype "passive"))
    )
    (net (code "85") (name "Net-(R30-Pad1)") (class "Default")
      (node (ref "R30") (pin "1") (pinfunction "1_1") (pintype "passive"))
      (node (ref "R32") (pin "2") (pinfunction "2_2") (pintype "passive"))
    )
    (net (code "86") (name "Net-(R31-Pad1)") (class "Default")
      (node (ref "R31") (pin "1") (pinfunction "1_1") (pintype "passive"))
      (node (ref "R33") (pin "2") (pinfunction "2_2") (pintype "passive"))
    )
    (net (code "87") (name "Net-(U2-CP1)") (class "Default")
      (node (ref "C20") (pin "2") (pinfunction "2_2") (pintype "passive"))
      (node (ref "TP2") (pin "1") (pintype "passive"))
      (node (ref "U2") (pin "46") (pinfunction "CP1_46") (pintype "bidirectional"))
    )
    (net (code "88") (name "Net-(U2-REG18)") (class "Default")
      (node (ref "C23") (pin "2") (pinfunction "2_2") (pintype "passive"))
      (node (ref "C24") (pin "2") (pinfunction "2_2") (pintype "passive"))
      (node (ref "TP7") (pin "1") (pintype "passive"))
      (node (ref "U2") (pin "24") (pinfunction "REG18_24") (pintype "power_in"))
    )
    (net (code "89") (name "Net-(U2-RST_SHUT)") (class "Default")
      (node (ref "C22") (pin "2") (pinfunction "2_2") (pintype "passive"))
      (node (ref "R38") (pin "1") (pinfunction "1_1") (pintype "passive"))
      (node (ref "U2") (pin "33") (pinfunction "RST_SHUT_33") (pintype "input"))
    )
    (net (code "90") (name "Net-(U3-VOUT)") (class "Default")
      (node (ref "R2") (pin "1") (pinfunction "1_1") (pintype "passive"))
      (node (ref "U3") (pin "2") (pinfunction "VOUT_2") (pintype "passive"))
    )
    (net (code "91") (name "Net-(U7-BST)") (class "Default")
      (node (ref "C7") (pin "2") (pinfunction "2_2") (pintype "passive"))
      (node (ref "U7") (pin "1") (pinfunction "BST_1") (pintype "passive"))
    )
    (net (code "92") (name "Net-(U7-ON{slash}~{OFF})") (class "Default")
      (node (ref "C35") (pin "2") (pinfunction "2_2") (pintype "passive"))
      (node (ref "R63") (pin "1") (pinfunction "1_1") (pintype "passive"))
      (node (ref "R73") (pin "2") (pinfunction "2_2") (pintype "passive"))
      (node (ref "U7") (pin "5") (pinfunction "ON/~{OFF}_5") (pintype "passive"))
    )
    (net (code "93") (name "Net-(U7-VD)") (class "Default")
      (node (ref "C36") (pin "2") (pinfunction "2_2") (pintype "passive"))
      (node (ref "U7") (pin "2") (pinfunction "VD_2") (pintype "passive"))
    )
    (net (code "94") (name "REG1") (class "Default")
      (node (ref "C21") (pin "1") (pinfunction "1_1") (pintype "passive"))
      (node (ref "PB1") (pin "2") (pinfunction "2_2") (pintype "passive"))
      (node (ref "R39") (pin "2") (pinfunction "2_2") (pintype "passive"))
      (node (ref "R51") (pin "2") (pinfunction "2_2") (pintype "passive"))
      (node (ref "U2") (pin "35") (pinfunction "REG1_35") (pintype "power_in"))
    )
    (net (code "95") (name "REG2") (class "Default")
      (node (ref "C32") (pin "1") (pinfunction "1_1") (pintype "passive"))
      (node (ref "R54") (pin "2") (pinfunction "2_2") (pintype "passive"))
      (node (ref "U2") (pin "34") (pinfunction "REG2_34") (pintype "power_in"))
    )
    (net (code "96") (name "unconnected-(U2-CHG-Pad45)") (class "Default")
      (node (ref "U2") (pin "45") (pinfunction "CHG_45") (pintype "output+no_connect"))
    )
    (net (code "97") (name "unconnected-(U2-DSG-Pad43)") (class "Default")
      (node (ref "U2") (pin "43") (pinfunction "DSG_43") (pintype "output+no_connect"))
    )
    (net (code "98") (name "unconnected-(U2-FUSE-Pad38)") (class "Default")
      (node (ref "U2") (pin "38") (pinfunction "FUSE_38") (pintype "input+no_connect"))
    )
    (net (code "99") (name "unconnected-(U2-NC-Pad19)") (class "Default")
      (node (ref "U2") (pin "19") (pinfunction "NC_19") (pintype "passive+no_connect"))
    )
    (net (code "100") (name "unconnected-(U2-NC-Pad44)") (class "Default")
      (node (ref "U2") (pin "44") (pinfunction "NC_44") (pintype "passive+no_connect"))
    )
    (net (code "101") (name "unconnected-(U2-PCHG-Pad40)") (class "Default")
      (node (ref "U2") (pin "40") (pinfunction "PCHG_40") (pintype "output+no_connect"))
    )
    (net (code "102") (name "unconnected-(U2-PDSG-Pad39)") (class "Default")
      (node (ref "U2") (pin "39") (pinfunction "PDSG_39") (pintype "output+no_connect"))
    )
  )
)
